# ESP32FC.net
KiCad netlist of a schematic drawn in EasyEDA
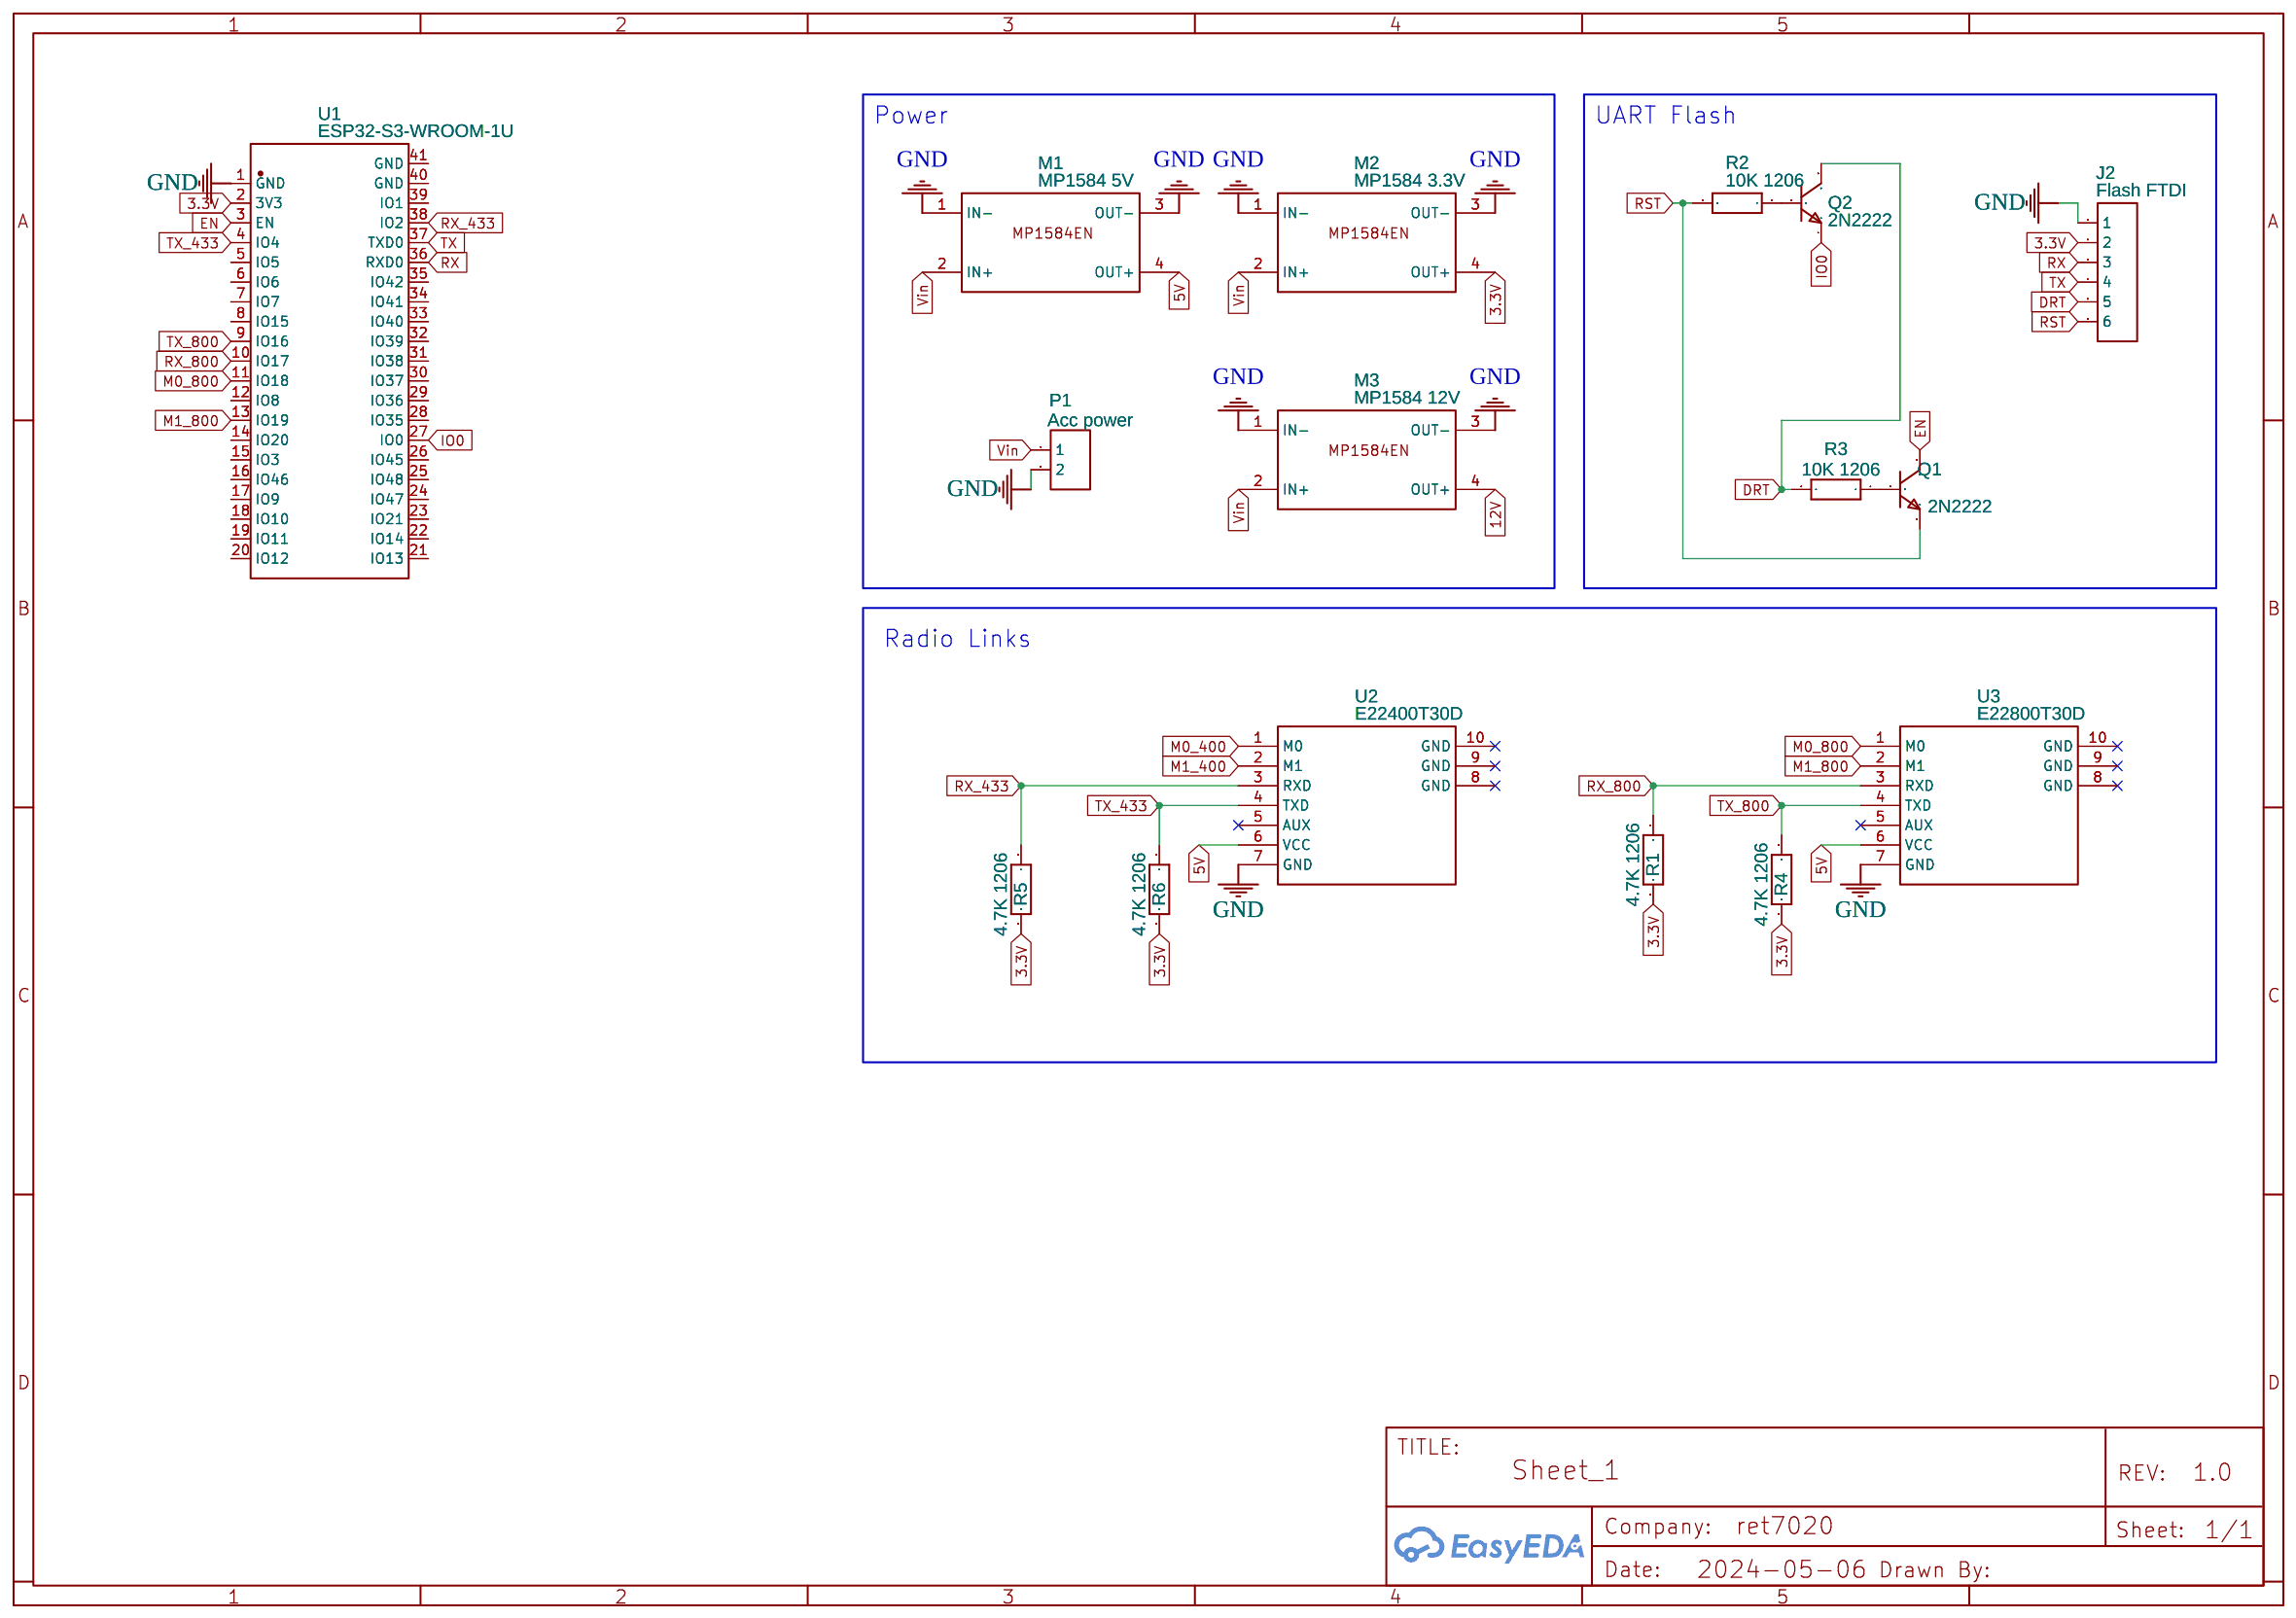
[diagram p0: schematic sheet]

(export (version "E")
  (design (tool "Eeschema 10.0.6"))
  (components
    (comp (ref "J2") (value "Flash FTDI") (libsource (lib "") (part "HDR-M-2.54_1x6")))
    (comp (ref "M1")
      (value "MP1584 5V")
      (fields (field (name "Manufacturer Part") "MP1584EN"))
      (libsource (lib "") (part "MP1584EN copy"))
    )
    (comp (ref "M2")
      (value "MP1584 3.3V")
      (fields (field (name "Manufacturer Part") "MP1584EN"))
      (libsource (lib "") (part "MP1584EN copy"))
    )
    (comp (ref "M3")
      (value "MP1584 12V")
      (fields (field (name "Manufacturer Part") "MP1584EN"))
      (libsource (lib "") (part "MP1584EN copy"))
    )
    (comp (ref "P1") (value "Acc power") (libsource (lib "") (part "CONN-TH_2P-P5.08")))
    (comp (ref "Q1")
      (value "2N2222")
      (fields (field (name "Manufacturer Part") "2N2222A") (field (name "Manufacturer") "ST(先科)"))
      (libsource (lib "") (part "2N2222"))
    )
    (comp (ref "Q2")
      (value "2N2222")
      (fields (field (name "Manufacturer Part") "2N2222A") (field (name "Manufacturer") "ST(先科)"))
      (libsource (lib "") (part "2N2222"))
    )
    (comp (ref "R1") (value "4.7K 1206") (libsource (lib "") (part "Resistor-SMD-1206")))
    (comp (ref "R2") (value "10K 1206") (libsource (lib "") (part "Resistor-SMD-1206_1")))
    (comp (ref "R3") (value "10K 1206") (libsource (lib "") (part "Resistor-SMD-1206_1")))
    (comp (ref "R4") (value "4.7K 1206") (libsource (lib "") (part "Resistor-SMD-1206")))
    (comp (ref "R5") (value "4.7K 1206") (libsource (lib "") (part "Resistor-SMD-1206")))
    (comp (ref "R6") (value "4.7K 1206") (libsource (lib "") (part "Resistor-SMD-1206")))
    (comp (ref "U1") (value "ESP32-S3-WROOM-1U") (libsource (lib "") (part "ESP32-S3-WROOM-1U")))
    (comp (ref "U2") (value "E22400T30D") (libsource (lib "") (part "GW-Ebyte-E22400T22D-TTL-LoRa")))
    (comp (ref "U3") (value "E22800T30D") (libsource (lib "") (part "GW-Ebyte-E22400T22D-TTL-LoRa")))
  )
  (nets
    (net (code "1") (name "3.3V") (class "Default")
      (node (ref "J2") (pin "2") (pinfunction "2_2") (pintype "input"))
      (node (ref "M2") (pin "4") (pinfunction "OUT+_4") (pintype "unspecified"))
      (node (ref "R1") (pin "2") (pinfunction "2_2") (pintype "unspecified"))
      (node (ref "R4") (pin "2") (pinfunction "2_2") (pintype "unspecified"))
      (node (ref "R5") (pin "2") (pinfunction "2_2") (pintype "unspecified"))
      (node (ref "R6") (pin "2") (pinfunction "2_2") (pintype "unspecified"))
      (node (ref "U1") (pin "2") (pinfunction "3V3_2") (pintype "unspecified"))
    )
    (net (code "2") (name "5V") (class "Default")
      (node (ref "M1") (pin "4") (pinfunction "OUT+_4") (pintype "unspecified"))
      (node (ref "U2") (pin "6") (pinfunction "VCC_6") (pintype "unspecified"))
      (node (ref "U3") (pin "6") (pinfunction "VCC_6") (pintype "unspecified"))
    )
    (net (code "3") (name "12V") (class "Default")
      (node (ref "M3") (pin "4") (pinfunction "OUT+_4") (pintype "unspecified"))
    )
    (net (code "4") (name "DRT") (class "Default")
      (node (ref "J2") (pin "5") (pinfunction "5_5") (pintype "input"))
      (node (ref "Q2") (pin "3") (pinfunction "C_3") (pintype "unspecified"))
      (node (ref "R3") (pin "2") (pinfunction "2_2") (pintype "unspecified"))
    )
    (net (code "5") (name "EN") (class "Default")
      (node (ref "Q1") (pin "3") (pinfunction "C_3") (pintype "unspecified"))
      (node (ref "U1") (pin "3") (pinfunction "EN_3") (pintype "unspecified"))
    )
    (net (code "6") (name "GND") (class "Default")
      (node (ref "J2") (pin "1") (pinfunction "1_1") (pintype "input"))
      (node (ref "M1") (pin "1") (pinfunction "IN-_1") (pintype "unspecified"))
      (node (ref "M1") (pin "3") (pinfunction "OUT-_3") (pintype "unspecified"))
      (node (ref "M2") (pin "1") (pinfunction "IN-_1") (pintype "unspecified"))
      (node (ref "M2") (pin "3") (pinfunction "OUT-_3") (pintype "unspecified"))
      (node (ref "M3") (pin "1") (pinfunction "IN-_1") (pintype "unspecified"))
      (node (ref "M3") (pin "3") (pinfunction "OUT-_3") (pintype "unspecified"))
      (node (ref "P1") (pin "2") (pinfunction "2_2") (pintype "unspecified"))
      (node (ref "U1") (pin "1") (pinfunction "GND_1") (pintype "unspecified"))
      (node (ref "U2") (pin "7") (pinfunction "GND_7") (pintype "unspecified"))
      (node (ref "U3") (pin "7") (pinfunction "GND_7") (pintype "unspecified"))
    )
    (net (code "7") (name "IO0") (class "Default")
      (node (ref "Q2") (pin "1") (pinfunction "E_1") (pintype "unspecified"))
      (node (ref "U1") (pin "27") (pinfunction "IO0_27") (pintype "unspecified"))
    )
    (net (code "8") (name "M0_400") (class "Default")
      (node (ref "U2") (pin "1") (pinfunction "M0_1") (pintype "unspecified"))
    )
    (net (code "9") (name "M0_800") (class "Default")
      (node (ref "U1") (pin "11") (pinfunction "IO18_11") (pintype "unspecified"))
      (node (ref "U3") (pin "1") (pinfunction "M0_1") (pintype "unspecified"))
    )
    (net (code "10") (name "M1_400") (class "Default")
      (node (ref "U2") (pin "2") (pinfunction "M1_2") (pintype "unspecified"))
    )
    (net (code "11") (name "M1_800") (class "Default")
      (node (ref "U1") (pin "13") (pinfunction "IO19_13") (pintype "unspecified"))
      (node (ref "U3") (pin "2") (pinfunction "M1_2") (pintype "unspecified"))
    )
    (net (code "12") (name "Net-(Q1-B)") (class "Default")
      (node (ref "Q1") (pin "2") (pinfunction "B_2") (pintype "unspecified"))
      (node (ref "R3") (pin "1") (pinfunction "1_1") (pintype "unspecified"))
    )
    (net (code "13") (name "Net-(Q2-B)") (class "Default")
      (node (ref "Q2") (pin "2") (pinfunction "B_2") (pintype "unspecified"))
      (node (ref "R2") (pin "1") (pinfunction "1_1") (pintype "unspecified"))
    )
    (net (code "14") (name "RST") (class "Default")
      (node (ref "J2") (pin "6") (pinfunction "6_6") (pintype "input"))
      (node (ref "Q1") (pin "1") (pinfunction "E_1") (pintype "unspecified"))
      (node (ref "R2") (pin "2") (pinfunction "2_2") (pintype "unspecified"))
    )
    (net (code "15") (name "RX") (class "Default")
      (node (ref "J2") (pin "3") (pinfunction "3_3") (pintype "input"))
      (node (ref "U1") (pin "36") (pinfunction "RXD0_36") (pintype "unspecified"))
    )
    (net (code "16") (name "RX_433") (class "Default")
      (node (ref "R5") (pin "1") (pinfunction "1_1") (pintype "unspecified"))
      (node (ref "U1") (pin "38") (pinfunction "IO2_38") (pintype "unspecified"))
      (node (ref "U2") (pin "3") (pinfunction "RXD_3") (pintype "unspecified"))
    )
    (net (code "17") (name "RX_800") (class "Default")
      (node (ref "R1") (pin "1") (pinfunction "1_1") (pintype "unspecified"))
      (node (ref "U1") (pin "10") (pinfunction "IO17_10") (pintype "unspecified"))
      (node (ref "U3") (pin "3") (pinfunction "RXD_3") (pintype "unspecified"))
    )
    (net (code "18") (name "TX") (class "Default")
      (node (ref "J2") (pin "4") (pinfunction "4_4") (pintype "input"))
      (node (ref "U1") (pin "37") (pinfunction "TXD0_37") (pintype "unspecified"))
    )
    (net (code "19") (name "TX_433") (class "Default")
      (node (ref "R6") (pin "1") (pinfunction "1_1") (pintype "unspecified"))
      (node (ref "U1") (pin "4") (pinfunction "IO4_4") (pintype "unspecified"))
      (node (ref "U2") (pin "4") (pinfunction "TXD_4") (pintype "unspecified"))
    )
    (net (code "20") (name "TX_800") (class "Default")
      (node (ref "R4") (pin "1") (pinfunction "1_1") (pintype "unspecified"))
      (node (ref "U1") (pin "9") (pinfunction "IO16_9") (pintype "unspecified"))
      (node (ref "U3") (pin "4") (pinfunction "TXD_4") (pintype "unspecified"))
    )
    (net (code "21") (name "Vin") (class "Default")
      (node (ref "M1") (pin "2") (pinfunction "IN+_2") (pintype "unspecified"))
      (node (ref "M2") (pin "2") (pinfunction "IN+_2") (pintype "unspecified"))
      (node (ref "M3") (pin "2") (pinfunction "IN+_2") (pintype "unspecified"))
      (node (ref "P1") (pin "1") (pinfunction "1_1") (pintype "unspecified"))
    )
    (net (code "22") (name "unconnected-(U1-GND-Pad40)") (class "Default")
      (node (ref "U1") (pin "40") (pinfunction "GND_40") (pintype "unspecified"))
    )
    (net (code "23") (name "unconnected-(U1-GND-Pad41)") (class "Default")
      (node (ref "U1") (pin "41") (pinfunction "GND_41") (pintype "unspecified"))
    )
    (net (code "24") (name "unconnected-(U1-IO1-Pad39)") (class "Default")
      (node (ref "U1") (pin "39") (pinfunction "IO1_39") (pintype "unspecified"))
    )
    (net (code "25") (name "unconnected-(U1-IO3-Pad15)") (class "Default")
      (node (ref "U1") (pin "15") (pinfunction "IO3_15") (pintype "unspecified"))
    )
    (net (code "26") (name "unconnected-(U1-IO5-Pad5)") (class "Default")
      (node (ref "U1") (pin "5") (pinfunction "IO5_5") (pintype "unspecified"))
    )
    (net (code "27") (name "unconnected-(U1-IO6-Pad6)") (class "Default")
      (node (ref "U1") (pin "6") (pinfunction "IO6_6") (pintype "unspecified"))
    )
    (net (code "28") (name "unconnected-(U1-IO7-Pad7)") (class "Default")
      (node (ref "U1") (pin "7") (pinfunction "IO7_7") (pintype "unspecified"))
    )
    (net (code "29") (name "unconnected-(U1-IO8-Pad12)") (class "Default")
      (node (ref "U1") (pin "12") (pinfunction "IO8_12") (pintype "unspecified"))
    )
    (net (code "30") (name "unconnected-(U1-IO9-Pad17)") (class "Default")
      (node (ref "U1") (pin "17") (pinfunction "IO9_17") (pintype "unspecified"))
    )
    (net (code "31") (name "unconnected-(U1-IO10-Pad18)") (class "Default")
      (node (ref "U1") (pin "18") (pinfunction "IO10_18") (pintype "unspecified"))
    )
    (net (code "32") (name "unconnected-(U1-IO11-Pad19)") (class "Default")
      (node (ref "U1") (pin "19") (pinfunction "IO11_19") (pintype "unspecified"))
    )
    (net (code "33") (name "unconnected-(U1-IO12-Pad20)") (class "Default")
      (node (ref "U1") (pin "20") (pinfunction "IO12_20") (pintype "unspecified"))
    )
    (net (code "34") (name "unconnected-(U1-IO13-Pad21)") (class "Default")
      (node (ref "U1") (pin "21") (pinfunction "IO13_21") (pintype "unspecified"))
    )
    (net (code "35") (name "unconnected-(U1-IO14-Pad22)") (class "Default")
      (node (ref "U1") (pin "22") (pinfunction "IO14_22") (pintype "unspecified"))
    )
    (net (code "36") (name "unconnected-(U1-IO15-Pad8)") (class "Default")
      (node (ref "U1") (pin "8") (pinfunction "IO15_8") (pintype "unspecified"))
    )
    (net (code "37") (name "unconnected-(U1-IO20-Pad14)") (class "Default")
      (node (ref "U1") (pin "14") (pinfunction "IO20_14") (pintype "unspecified"))
    )
    (net (code "38") (name "unconnected-(U1-IO21-Pad23)") (class "Default")
      (node (ref "U1") (pin "23") (pinfunction "IO21_23") (pintype "unspecified"))
    )
    (net (code "39") (name "unconnected-(U1-IO35-Pad28)") (class "Default")
      (node (ref "U1") (pin "28") (pinfunction "IO35_28") (pintype "unspecified"))
    )
    (net (code "40") (name "unconnected-(U1-IO36-Pad29)") (class "Default")
      (node (ref "U1") (pin "29") (pinfunction "IO36_29") (pintype "unspecified"))
    )
    (net (code "41") (name "unconnected-(U1-IO37-Pad30)") (class "Default")
      (node (ref "U1") (pin "30") (pinfunction "IO37_30") (pintype "unspecified"))
    )
    (net (code "42") (name "unconnected-(U1-IO38-Pad31)") (class "Default")
      (node (ref "U1") (pin "31") (pinfunction "IO38_31") (pintype "unspecified"))
    )
    (net (code "43") (name "unconnected-(U1-IO39-Pad32)") (class "Default")
      (node (ref "U1") (pin "32") (pinfunction "IO39_32") (pintype "unspecified"))
    )
    (net (code "44") (name "unconnected-(U1-IO40-Pad33)") (class "Default")
      (node (ref "U1") (pin "33") (pinfunction "IO40_33") (pintype "unspecified"))
    )
    (net (code "45") (name "unconnected-(U1-IO41-Pad34)") (class "Default")
      (node (ref "U1") (pin "34") (pinfunction "IO41_34") (pintype "unspecified"))
    )
    (net (code "46") (name "unconnected-(U1-IO42-Pad35)") (class "Default")
      (node (ref "U1") (pin "35") (pinfunction "IO42_35") (pintype "unspecified"))
    )
    (net (code "47") (name "unconnected-(U1-IO45-Pad26)") (class "Default")
      (node (ref "U1") (pin "26") (pinfunction "IO45_26") (pintype "unspecified"))
    )
    (net (code "48") (name "unconnected-(U1-IO46-Pad16)") (class "Default")
      (node (ref "U1") (pin "16") (pinfunction "IO46_16") (pintype "unspecified"))
    )
    (net (code "49") (name "unconnected-(U1-IO47-Pad24)") (class "Default")
      (node (ref "U1") (pin "24") (pinfunction "IO47_24") (pintype "unspecified"))
    )
    (net (code "50") (name "unconnected-(U1-IO48-Pad25)") (class "Default")
      (node (ref "U1") (pin "25") (pinfunction "IO48_25") (pintype "unspecified"))
    )
    (net (code "51") (name "unconnected-(U2-AUX-Pad5)") (class "Default")
      (node (ref "U2") (pin "5") (pinfunction "AUX_5") (pintype "unspecified+no_connect"))
    )
    (net (code "52") (name "unconnected-(U2-GND-Pad8)") (class "Default")
      (node (ref "U2") (pin "8") (pinfunction "GND_8") (pintype "unspecified+no_connect"))
    )
    (net (code "53") (name "unconnected-(U2-GND-Pad9)") (class "Default")
      (node (ref "U2") (pin "9") (pinfunction "GND_9") (pintype "unspecified+no_connect"))
    )
    (net (code "54") (name "unconnected-(U2-GND-Pad10)") (class "Default")
      (node (ref "U2") (pin "10") (pinfunction "GND_10") (pintype "unspecified+no_connect"))
    )
    (net (code "55") (name "unconnected-(U3-AUX-Pad5)") (class "Default")
      (node (ref "U3") (pin "5") (pinfunction "AUX_5") (pintype "unspecified+no_connect"))
    )
    (net (code "56") (name "unconnected-(U3-GND-Pad8)") (class "Default")
      (node (ref "U3") (pin "8") (pinfunction "GND_8") (pintype "unspecified+no_connect"))
    )
    (net (code "57") (name "unconnected-(U3-GND-Pad9)") (class "Default")
      (node (ref "U3") (pin "9") (pinfunction "GND_9") (pintype "unspecified+no_connect"))
    )
    (net (code "58") (name "unconnected-(U3-GND-Pad10)") (class "Default")
      (node (ref "U3") (pin "10") (pinfunction "GND_10") (pintype "unspecified+no_connect"))
    )
  )
)
